# pqc-rev1_1.net
KiCad netlist of a schematic drawn in EAGLE
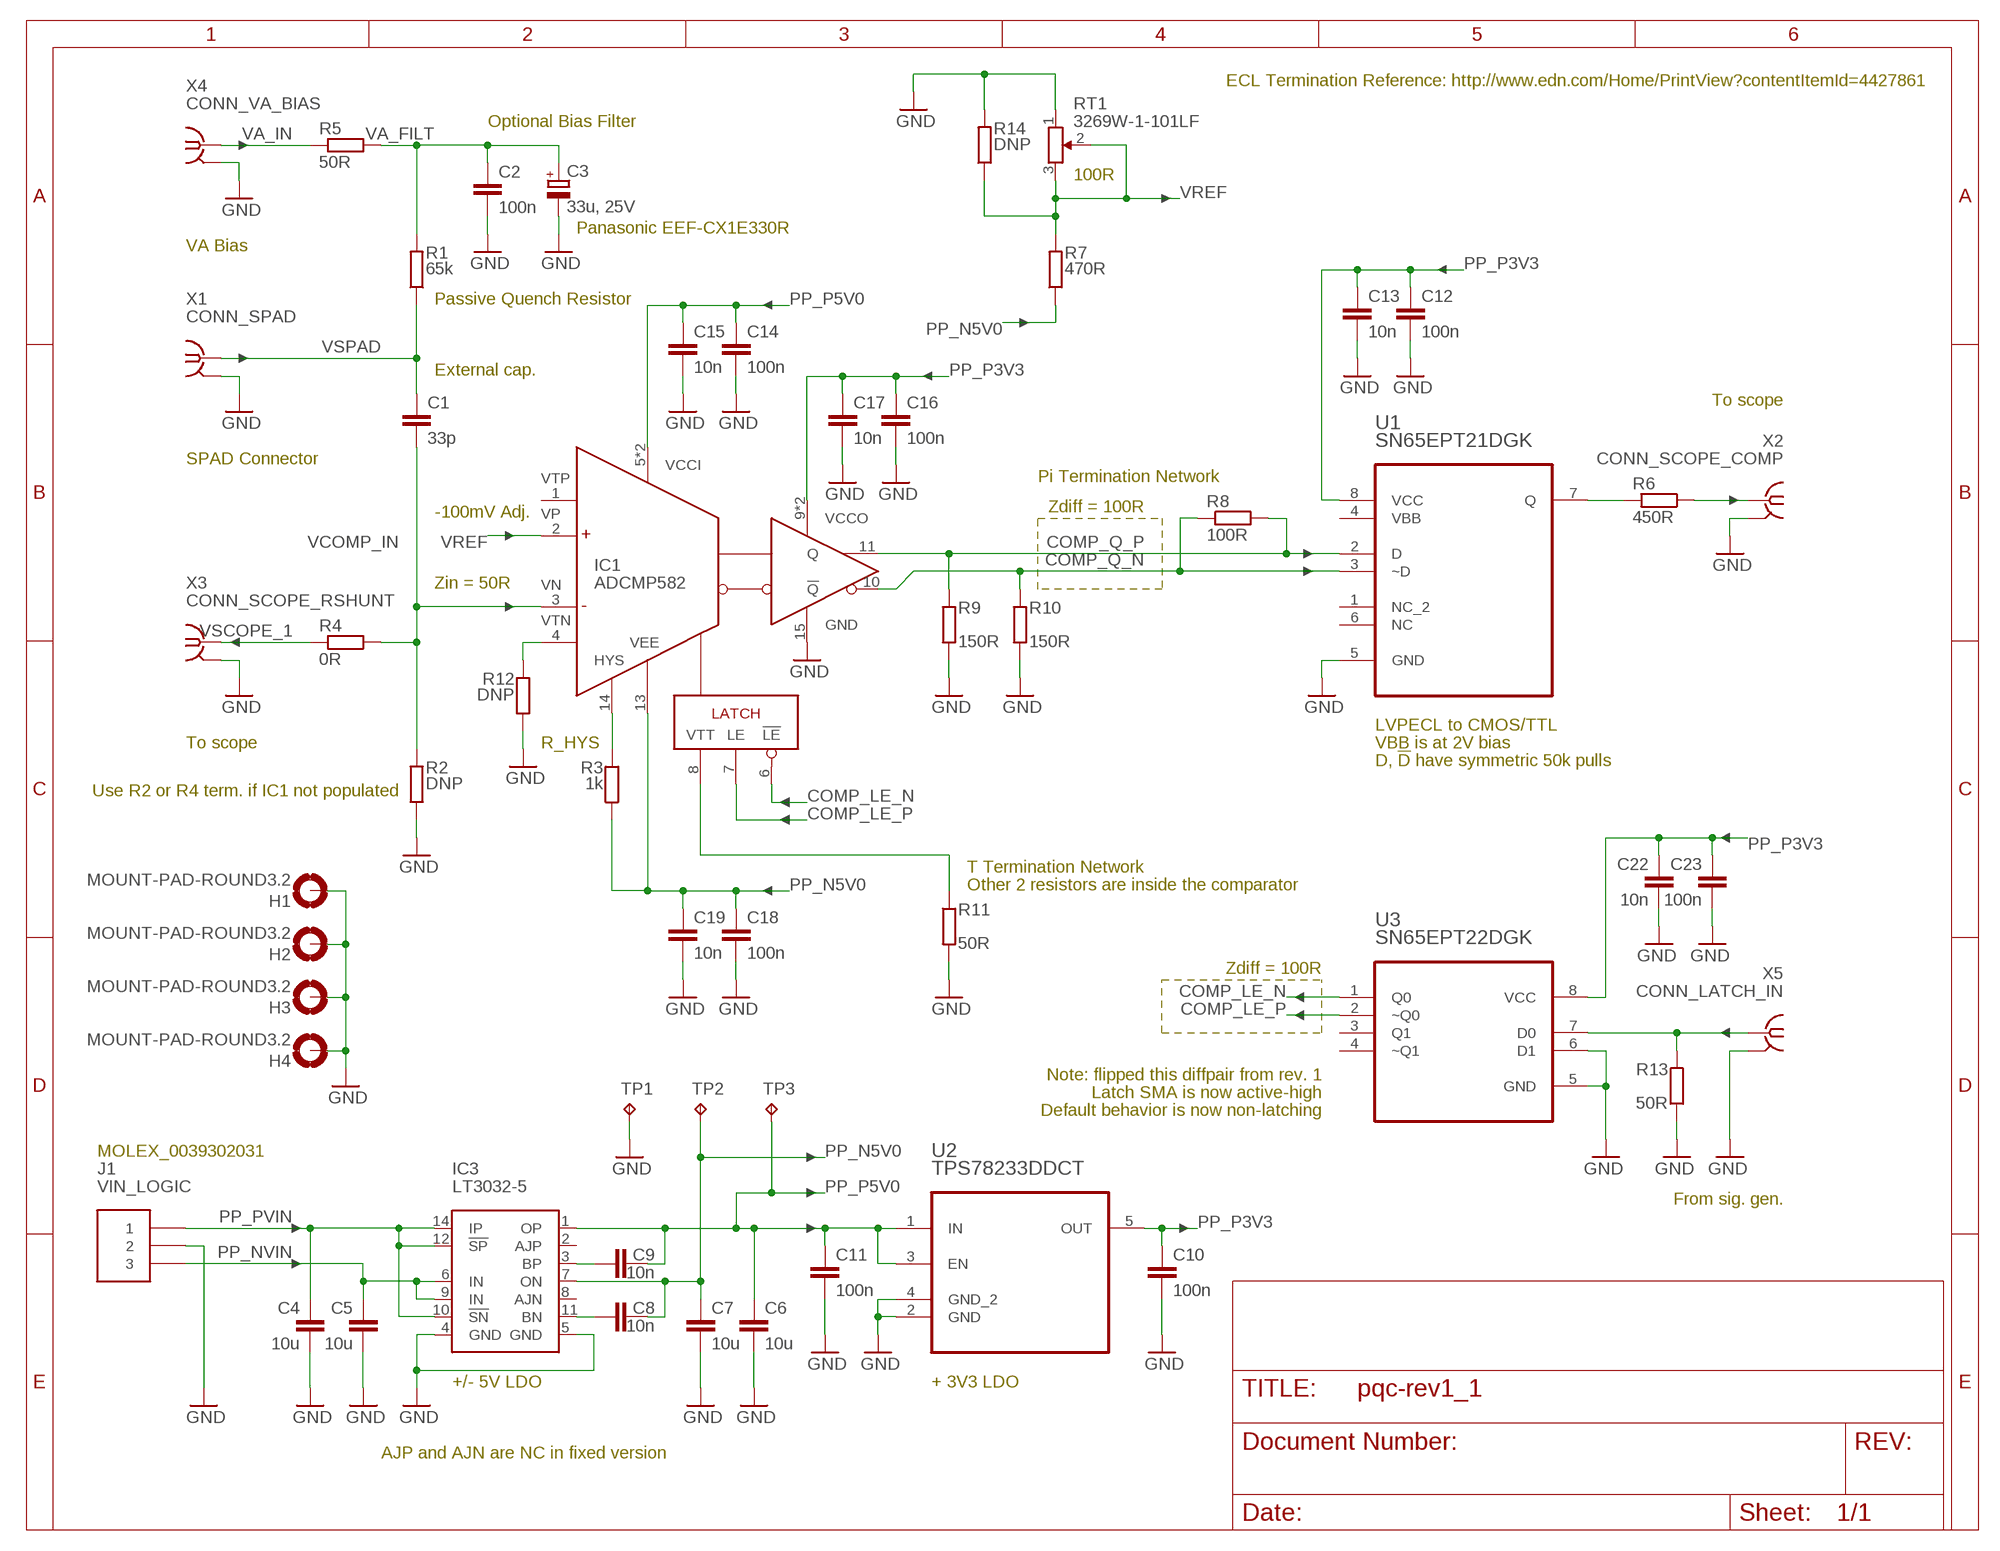
[diagram p0: schematic, sheet 1]

(export (version "E")
  (design (tool "Eeschema 10.0.6"))
  (components
    (comp (ref "C1")
      (value "33p")
      (footprint "eagle-import:C0805")
      (libsource (lib "eagle-import") (part "C-EUC0805"))
    )
    (comp (ref "C2")
      (value "100n")
      (footprint "eagle-import:C0805")
      (libsource (lib "eagle-import") (part "C-EUC0805"))
    )
    (comp (ref "C3")
      (value "33u, 25V")
      (footprint "eagle-import:CT7343")
      (libsource (lib "eagle-import") (part "CPOL-EUCT7343"))
    )
    (comp (ref "C4")
      (value "10u")
      (footprint "eagle-import:C1206")
      (libsource (lib "eagle-import") (part "C-EUC1206"))
    )
    (comp (ref "C5")
      (value "10u")
      (footprint "eagle-import:C1206")
      (libsource (lib "eagle-import") (part "C-EUC1206"))
    )
    (comp (ref "C6")
      (value "10u")
      (footprint "eagle-import:C1206")
      (libsource (lib "eagle-import") (part "C-EUC1206"))
    )
    (comp (ref "C7")
      (value "10u")
      (footprint "eagle-import:C1206")
      (libsource (lib "eagle-import") (part "C-EUC1206"))
    )
    (comp (ref "C8")
      (value "10n")
      (footprint "eagle-import:C0603")
      (libsource (lib "eagle-import") (part "C-EUC0603"))
    )
    (comp (ref "C9")
      (value "10n")
      (footprint "eagle-import:C0603")
      (libsource (lib "eagle-import") (part "C-EUC0603"))
    )
    (comp (ref "C10")
      (value "100n")
      (footprint "eagle-import:C0603")
      (libsource (lib "eagle-import") (part "C-EUC0603"))
    )
    (comp (ref "C11")
      (value "100n")
      (footprint "eagle-import:C0603")
      (libsource (lib "eagle-import") (part "C-EUC0603"))
    )
    (comp (ref "C12")
      (value "100n")
      (footprint "eagle-import:C0603")
      (libsource (lib "eagle-import") (part "C-EUC0603"))
    )
    (comp (ref "C13")
      (value "10n")
      (footprint "eagle-import:C0603")
      (libsource (lib "eagle-import") (part "C-EUC0603"))
    )
    (comp (ref "C14")
      (value "100n")
      (footprint "eagle-import:C0603")
      (libsource (lib "eagle-import") (part "C-EUC0603"))
    )
    (comp (ref "C15")
      (value "10n")
      (footprint "eagle-import:C0603")
      (libsource (lib "eagle-import") (part "C-EUC0603"))
    )
    (comp (ref "C16")
      (value "100n")
      (footprint "eagle-import:C0603")
      (libsource (lib "eagle-import") (part "C-EUC0603"))
    )
    (comp (ref "C17")
      (value "10n")
      (footprint "eagle-import:C0603")
      (libsource (lib "eagle-import") (part "C-EUC0603"))
    )
    (comp (ref "C18")
      (value "100n")
      (footprint "eagle-import:C0603")
      (libsource (lib "eagle-import") (part "C-EUC0603"))
    )
    (comp (ref "C19")
      (value "10n")
      (footprint "eagle-import:C0603")
      (libsource (lib "eagle-import") (part "C-EUC0603"))
    )
    (comp (ref "C22")
      (value "10n")
      (footprint "eagle-import:C0603")
      (libsource (lib "eagle-import") (part "C-EUC0603"))
    )
    (comp (ref "C23")
      (value "100n")
      (footprint "eagle-import:C0603")
      (libsource (lib "eagle-import") (part "C-EUC0603"))
    )
    (comp (ref "H1")
      (value "MOUNT-PAD-ROUND3.2")
      (footprint "eagle-import:3,2-PAD")
      (libsource (lib "eagle-import") (part "MOUNT-PAD-ROUND3.2"))
    )
    (comp (ref "H2")
      (value "MOUNT-PAD-ROUND3.2")
      (footprint "eagle-import:3,2-PAD")
      (libsource (lib "eagle-import") (part "MOUNT-PAD-ROUND3.2"))
    )
    (comp (ref "H3")
      (value "MOUNT-PAD-ROUND3.2")
      (footprint "eagle-import:3,2-PAD")
      (libsource (lib "eagle-import") (part "MOUNT-PAD-ROUND3.2"))
    )
    (comp (ref "H4")
      (value "MOUNT-PAD-ROUND3.2")
      (footprint "eagle-import:3,2-PAD")
      (libsource (lib "eagle-import") (part "MOUNT-PAD-ROUND3.2"))
    )
    (comp (ref "IC1")
      (value "ADCMP582")
      (footprint "eagle-import:QFN50P300X300X80-16N")
      (libsource (lib "eagle-import") (part "ADCMP582"))
    )
    (comp (ref "IC3")
      (value "LT3032-5")
      (footprint "eagle-import:DFN14-4X3DE")
      (libsource (lib "eagle-import") (part "LT3032"))
    )
    (comp (ref "J1")
      (value "VIN_LOGIC")
      (footprint "eagle-import:CONN_MOLEX_3PIN_MINI-FIT_JR")
      (libsource (lib "eagle-import") (part "CONN_MOLEX_3PIN_MINI-FIT_JR"))
    )
    (comp (ref "R1")
      (value "65k")
      (footprint "eagle-import:R0805")
      (libsource (lib "eagle-import") (part "R-EU_R0805"))
    )
    (comp (ref "R2")
      (value "DNP")
      (footprint "eagle-import:R0603")
      (libsource (lib "eagle-import") (part "R-EU_R0603"))
    )
    (comp (ref "R3")
      (value "1k")
      (footprint "eagle-import:R0805")
      (libsource (lib "eagle-import") (part "R-EU_R0805"))
    )
    (comp (ref "R4")
      (value "0R")
      (footprint "eagle-import:R0603")
      (libsource (lib "eagle-import") (part "R-EU_R0603"))
    )
    (comp (ref "R5")
      (value "50R")
      (footprint "eagle-import:R0805")
      (libsource (lib "eagle-import") (part "R-EU_R0805"))
    )
    (comp (ref "R6")
      (value "450R")
      (footprint "eagle-import:R0603")
      (libsource (lib "eagle-import") (part "R-EU_R0603"))
    )
    (comp (ref "R7")
      (value "470R")
      (footprint "eagle-import:R0805")
      (libsource (lib "eagle-import") (part "R-EU_R0805"))
    )
    (comp (ref "R8")
      (value "100R")
      (footprint "eagle-import:R0603")
      (libsource (lib "eagle-import") (part "R-EU_R0603"))
    )
    (comp (ref "R9")
      (value "150R")
      (footprint "eagle-import:R0603")
      (libsource (lib "eagle-import") (part "R-EU_R0603"))
    )
    (comp (ref "R10")
      (value "150R")
      (footprint "eagle-import:R0603")
      (libsource (lib "eagle-import") (part "R-EU_R0603"))
    )
    (comp (ref "R11")
      (value "50R")
      (footprint "eagle-import:R0603")
      (libsource (lib "eagle-import") (part "R-EU_R0603"))
    )
    (comp (ref "R12")
      (value "DNP")
      (footprint "eagle-import:R0603")
      (libsource (lib "eagle-import") (part "R-EU_R0603"))
    )
    (comp (ref "R13")
      (value "50R")
      (footprint "eagle-import:R0603")
      (libsource (lib "eagle-import") (part "R-EU_R0603"))
    )
    (comp (ref "R14")
      (value "DNP")
      (footprint "eagle-import:R0805")
      (libsource (lib "eagle-import") (part "R-EU_R0805"))
    )
    (comp (ref "RT1")
      (value "3269W-1-101LF")
      (footprint "eagle-import:3269W")
      (libsource (lib "eagle-import") (part "BOURNS_3269WX"))
    )
    (comp (ref "TP1")
      (value "TPTP20R")
      (footprint "eagle-import:TP20R")
      (libsource (lib "eagle-import") (part "TPTP20R"))
    )
    (comp (ref "TP2")
      (value "TPTP20R")
      (footprint "eagle-import:TP20R")
      (libsource (lib "eagle-import") (part "TPTP20R"))
    )
    (comp (ref "TP3")
      (value "TPTP20R")
      (footprint "eagle-import:TP20R")
      (libsource (lib "eagle-import") (part "TPTP20R"))
    )
    (comp (ref "U1")
      (value "SN65EPT21DGK")
      (footprint "eagle-import:SOP65P490X110-8N")
      (libsource (lib "eagle-import") (part "SN65EPT21DGK"))
    )
    (comp (ref "U2")
      (value "TPS78233DDCT")
      (footprint "eagle-import:SOT95P280X110-5N")
      (libsource (lib "eagle-import") (part "TPS78233DDCT"))
    )
    (comp (ref "U3")
      (value "SN65EPT22DGK")
      (footprint "eagle-import:SOP65P490X110-8N")
      (libsource (lib "eagle-import") (part "SN65EPT22DGK"))
    )
    (comp (ref "X1")
      (value "CONN_SPAD")
      (footprint "eagle-import:J502-ND-142-0711-871_876")
      (fields (field (name "MF") "JOHNSON COMPONENTS") (field (name "MPN") "142-0711-871"))
      (libsource (lib "eagle-import") (part "SMA-142-0711-871/876"))
    )
    (comp (ref "X2")
      (value "CONN_SCOPE_COMP")
      (footprint "eagle-import:J502-ND-142-0711-871_876")
      (fields (field (name "MF") "JOHNSON COMPONENTS") (field (name "MPN") "142-0711-871"))
      (libsource (lib "eagle-import") (part "SMA-142-0711-871/876"))
    )
    (comp (ref "X3")
      (value "CONN_SCOPE_RSHUNT")
      (footprint "eagle-import:J502-ND-142-0711-871_876")
      (fields (field (name "MF") "JOHNSON COMPONENTS") (field (name "MPN") "142-0711-871"))
      (libsource (lib "eagle-import") (part "SMA-142-0711-871/876"))
    )
    (comp (ref "X4")
      (value "CONN_VA_BIAS")
      (footprint "eagle-import:J502-ND-142-0711-871_876")
      (fields (field (name "MF") "JOHNSON COMPONENTS") (field (name "MPN") "142-0711-871"))
      (libsource (lib "eagle-import") (part "SMA-142-0711-871/876"))
    )
    (comp (ref "X5")
      (value "CONN_LATCH_IN")
      (footprint "eagle-import:J502-ND-142-0711-871_876")
      (fields
        (field (name "MF") "JOHNSON COMPONENTS")
        (field (name "MPN") "142-0711-871")
        (field (name "MF_1") "JOHNSON COMPONENTS")
        (field (name "MPN_1") "142-0711-871")
        (field (name "OC_FARNELL") "unknown")
        (field (name "OC_NEWARK") "01C1639")
      )
      (libsource (lib "eagle-import") (part "SMA-142-0711-871/876"))
    )
  )
  (nets
    (net (code "1") (name "/COMP_LE_N") (class "Default")
      (node (ref "IC1") (pin "6") (pinfunction "~{LE}_6") (pintype "bidirectional"))
      (node (ref "U3") (pin "1") (pinfunction "Q0_1") (pintype "output"))
    )
    (net (code "2") (name "/COMP_LE_P") (class "Default")
      (node (ref "IC1") (pin "7") (pinfunction "LE_7") (pintype "bidirectional"))
      (node (ref "U3") (pin "2") (pinfunction "~{Q0}_2") (pintype "output"))
    )
    (net (code "3") (name "/COMP_Q_N") (class "Default")
      (node (ref "IC1") (pin "10") (pinfunction "~{Q}_10") (pintype "bidirectional"))
      (node (ref "R10") (pin "1") (pinfunction "1_1") (pintype "passive"))
      (node (ref "R8") (pin "1") (pinfunction "1_1") (pintype "passive"))
      (node (ref "U1") (pin "3") (pinfunction "~{D}_3") (pintype "input"))
    )
    (net (code "4") (name "/COMP_Q_P") (class "Default")
      (node (ref "IC1") (pin "11") (pinfunction "Q_11") (pintype "bidirectional"))
      (node (ref "R8") (pin "2") (pinfunction "2_2") (pintype "passive"))
      (node (ref "R9") (pin "1") (pinfunction "1_1") (pintype "passive"))
      (node (ref "U1") (pin "2") (pinfunction "D_2") (pintype "input"))
    )
    (net (code "5") (name "/PP_N5V0") (class "Default")
      (node (ref "C18") (pin "1") (pinfunction "1_1") (pintype "passive"))
      (node (ref "C19") (pin "1") (pinfunction "1_1") (pintype "passive"))
      (node (ref "C7") (pin "1") (pinfunction "1_1") (pintype "passive"))
      (node (ref "C8") (pin "2") (pinfunction "2_2") (pintype "passive"))
      (node (ref "IC1") (pin "13") (pinfunction "VEE_13") (pintype "bidirectional"))
      (node (ref "IC3") (pin "7") (pinfunction "ON_7") (pintype "power_in"))
      (node (ref "R3") (pin "1") (pinfunction "1_1") (pintype "passive"))
      (node (ref "R7") (pin "1") (pinfunction "1_1") (pintype "passive"))
      (node (ref "TP2") (pin "TP") (pinfunction "TP_TP") (pintype "input"))
    )
    (net (code "6") (name "/PP_NVIN") (class "Default")
      (node (ref "C5") (pin "1") (pinfunction "1_1") (pintype "passive"))
      (node (ref "IC3") (pin "6") (pinfunction "IN_6") (pintype "power_in"))
      (node (ref "IC3") (pin "9") (pinfunction "IN_9") (pintype "power_in"))
      (node (ref "J1") (pin "3") (pinfunction "3_3") (pintype "bidirectional"))
    )
    (net (code "7") (name "/PP_P3V3") (class "Default")
      (node (ref "C10") (pin "1") (pinfunction "1_1") (pintype "passive"))
      (node (ref "C12") (pin "1") (pinfunction "1_1") (pintype "passive"))
      (node (ref "C13") (pin "1") (pinfunction "1_1") (pintype "passive"))
      (node (ref "C16") (pin "1") (pinfunction "1_1") (pintype "passive"))
      (node (ref "C17") (pin "1") (pinfunction "1_1") (pintype "passive"))
      (node (ref "C22") (pin "1") (pinfunction "1_1") (pintype "passive"))
      (node (ref "C23") (pin "1") (pinfunction "1_1") (pintype "passive"))
      (node (ref "IC1") (pin "12") (pinfunction "VCCO_12") (pintype "bidirectional"))
      (node (ref "IC1") (pin "9") (pinfunction "VCCO_9") (pintype "bidirectional"))
      (node (ref "U1") (pin "8") (pinfunction "VCC_8") (pintype "power_in"))
      (node (ref "U2") (pin "5") (pinfunction "OUT_5") (pintype "output"))
      (node (ref "U3") (pin "8") (pinfunction "VCC_8") (pintype "power_in"))
    )
    (net (code "8") (name "/PP_P5V0") (class "Default")
      (node (ref "C11") (pin "1") (pinfunction "1_1") (pintype "passive"))
      (node (ref "C14") (pin "1") (pinfunction "1_1") (pintype "passive"))
      (node (ref "C15") (pin "1") (pinfunction "1_1") (pintype "passive"))
      (node (ref "C6") (pin "1") (pinfunction "1_1") (pintype "passive"))
      (node (ref "C9") (pin "2") (pinfunction "2_2") (pintype "passive"))
      (node (ref "IC1") (pin "16") (pinfunction "VCCI_16") (pintype "bidirectional"))
      (node (ref "IC1") (pin "5") (pinfunction "VCCI_5") (pintype "bidirectional"))
      (node (ref "IC3") (pin "1") (pinfunction "OP_1") (pintype "power_in"))
      (node (ref "TP3") (pin "TP") (pinfunction "TP_TP") (pintype "input"))
      (node (ref "U2") (pin "1") (pinfunction "IN_1") (pintype "input"))
      (node (ref "U2") (pin "3") (pinfunction "EN_3") (pintype "input"))
    )
    (net (code "9") (name "/PP_PVIN") (class "Default")
      (node (ref "C4") (pin "1") (pinfunction "1_1") (pintype "passive"))
      (node (ref "IC3") (pin "10") (pinfunction "~{SN}_10") (pintype "bidirectional"))
      (node (ref "IC3") (pin "12") (pinfunction "~{SP}_12") (pintype "bidirectional"))
      (node (ref "IC3") (pin "14") (pinfunction "IP_14") (pintype "power_in"))
      (node (ref "J1") (pin "1") (pinfunction "1_1") (pintype "bidirectional"))
    )
    (net (code "10") (name "/VA_FILT") (class "Default")
      (node (ref "C2") (pin "1") (pinfunction "1_1") (pintype "passive"))
      (node (ref "C3") (pin "+") (pinfunction "+_+") (pintype "passive"))
      (node (ref "R1") (pin "2") (pinfunction "2_2") (pintype "passive"))
      (node (ref "R5") (pin "1") (pinfunction "1_1") (pintype "passive"))
    )
    (net (code "11") (name "/VA_IN") (class "Default")
      (node (ref "R5") (pin "2") (pinfunction "2_2") (pintype "passive"))
      (node (ref "X4") (pin "1") (pinfunction "1_1") (pintype "passive"))
    )
    (net (code "12") (name "/VBB") (class "Default")
      (node (ref "U1") (pin "4") (pinfunction "VBB_4") (pintype "power_in"))
    )
    (net (code "13") (name "/VCOMP_IN") (class "Default")
      (node (ref "C1") (pin "2") (pinfunction "2_2") (pintype "passive"))
      (node (ref "IC1") (pin "3") (pinfunction "VN_3") (pintype "bidirectional"))
      (node (ref "R2") (pin "2") (pinfunction "2_2") (pintype "passive"))
      (node (ref "R4") (pin "1") (pinfunction "1_1") (pintype "passive"))
    )
    (net (code "14") (name "/VREF") (class "Default")
      (node (ref "IC1") (pin "2") (pinfunction "VP_2") (pintype "bidirectional"))
      (node (ref "R14") (pin "1") (pinfunction "1_1") (pintype "passive"))
      (node (ref "R7") (pin "2") (pinfunction "2_2") (pintype "passive"))
      (node (ref "RT1") (pin "2") (pinfunction "2_2") (pintype "bidirectional"))
      (node (ref "RT1") (pin "3") (pinfunction "3_3") (pintype "bidirectional"))
    )
    (net (code "15") (name "/VSCOPE_1") (class "Default")
      (node (ref "R4") (pin "2") (pinfunction "2_2") (pintype "passive"))
      (node (ref "X3") (pin "1") (pinfunction "1_1") (pintype "passive"))
    )
    (net (code "16") (name "/VSPAD") (class "Default")
      (node (ref "C1") (pin "1") (pinfunction "1_1") (pintype "passive"))
      (node (ref "R1") (pin "1") (pinfunction "1_1") (pintype "passive"))
      (node (ref "X1") (pin "1") (pinfunction "1_1") (pintype "passive"))
    )
    (net (code "17") (name "GND") (class "Default")
      (node (ref "C10") (pin "2") (pinfunction "2_2") (pintype "passive"))
      (node (ref "C11") (pin "2") (pinfunction "2_2") (pintype "passive"))
      (node (ref "C12") (pin "2") (pinfunction "2_2") (pintype "passive"))
      (node (ref "C13") (pin "2") (pinfunction "2_2") (pintype "passive"))
      (node (ref "C14") (pin "2") (pinfunction "2_2") (pintype "passive"))
      (node (ref "C15") (pin "2") (pinfunction "2_2") (pintype "passive"))
      (node (ref "C16") (pin "2") (pinfunction "2_2") (pintype "passive"))
      (node (ref "C17") (pin "2") (pinfunction "2_2") (pintype "passive"))
      (node (ref "C18") (pin "2") (pinfunction "2_2") (pintype "passive"))
      (node (ref "C19") (pin "2") (pinfunction "2_2") (pintype "passive"))
      (node (ref "C2") (pin "2") (pinfunction "2_2") (pintype "passive"))
      (node (ref "C22") (pin "2") (pinfunction "2_2") (pintype "passive"))
      (node (ref "C23") (pin "2") (pinfunction "2_2") (pintype "passive"))
      (node (ref "C3") (pin "-") (pinfunction "-_-") (pintype "passive"))
      (node (ref "C4") (pin "2") (pinfunction "2_2") (pintype "passive"))
      (node (ref "C5") (pin "2") (pinfunction "2_2") (pintype "passive"))
      (node (ref "C6") (pin "2") (pinfunction "2_2") (pintype "passive"))
      (node (ref "C7") (pin "2") (pinfunction "2_2") (pintype "passive"))
      (node (ref "H1") (pin "B3,2") (pinfunction "MOUNT_B3,2") (pintype "passive"))
      (node (ref "H2") (pin "B3,2") (pinfunction "MOUNT_B3,2") (pintype "passive"))
      (node (ref "H3") (pin "B3,2") (pinfunction "MOUNT_B3,2") (pintype "passive"))
      (node (ref "H4") (pin "B3,2") (pinfunction "MOUNT_B3,2") (pintype "passive"))
      (node (ref "IC1") (pin "15") (pinfunction "GND_15") (pintype "bidirectional"))
      (node (ref "IC3") (pin "4") (pinfunction "GND_4") (pintype "power_in"))
      (node (ref "IC3") (pin "5") (pinfunction "GND_5") (pintype "power_in"))
      (node (ref "J1") (pin "2") (pinfunction "2_2") (pintype "bidirectional"))
      (node (ref "R10") (pin "2") (pinfunction "2_2") (pintype "passive"))
      (node (ref "R11") (pin "2") (pinfunction "2_2") (pintype "passive"))
      (node (ref "R12") (pin "1") (pinfunction "1_1") (pintype "passive"))
      (node (ref "R13") (pin "2") (pinfunction "2_2") (pintype "passive"))
      (node (ref "R14") (pin "2") (pinfunction "2_2") (pintype "passive"))
      (node (ref "R2") (pin "1") (pinfunction "1_1") (pintype "passive"))
      (node (ref "R9") (pin "2") (pinfunction "2_2") (pintype "passive"))
      (node (ref "RT1") (pin "1") (pinfunction "1_1") (pintype "bidirectional"))
      (node (ref "TP1") (pin "TP") (pinfunction "TP_TP") (pintype "input"))
      (node (ref "U1") (pin "5") (pinfunction "GND_5") (pintype "passive"))
      (node (ref "U2") (pin "2") (pinfunction "GND_2") (pintype "passive"))
      (node (ref "U2") (pin "4") (pinfunction "GND_2_4") (pintype "passive"))
      (node (ref "U3") (pin "5") (pinfunction "GND_5") (pintype "passive"))
      (node (ref "U3") (pin "6") (pinfunction "D1_6") (pintype "input"))
      (node (ref "X1") (pin "G@1") (pinfunction "GND_G@1") (pintype "power_in"))
      (node (ref "X2") (pin "G@1") (pinfunction "GND_G@1") (pintype "power_in"))
      (node (ref "X3") (pin "G@1") (pinfunction "GND_G@1") (pintype "power_in"))
      (node (ref "X4") (pin "G@1") (pinfunction "GND_G@1") (pintype "power_in"))
      (node (ref "X5") (pin "G@1") (pinfunction "GND_G@1") (pintype "power_in"))
    )
    (net (code "18") (name "Net-(IC1-HYS)") (class "Default")
      (node (ref "IC1") (pin "14") (pinfunction "HYS_14") (pintype "bidirectional"))
      (node (ref "R3") (pin "2") (pinfunction "2_2") (pintype "passive"))
    )
    (net (code "19") (name "Net-(IC1-VTN)") (class "Default")
      (node (ref "IC1") (pin "4") (pinfunction "VTN_4") (pintype "bidirectional"))
      (node (ref "R12") (pin "2") (pinfunction "2_2") (pintype "passive"))
    )
    (net (code "20") (name "Net-(IC1-VTT)") (class "Default")
      (node (ref "IC1") (pin "8") (pinfunction "VTT_8") (pintype "bidirectional"))
      (node (ref "R11") (pin "1") (pinfunction "1_1") (pintype "passive"))
    )
    (net (code "21") (name "Net-(IC3-BN)") (class "Default")
      (node (ref "C8") (pin "1") (pinfunction "1_1") (pintype "passive"))
      (node (ref "IC3") (pin "11") (pinfunction "BN_11") (pintype "bidirectional"))
    )
    (net (code "22") (name "Net-(IC3-BP)") (class "Default")
      (node (ref "C9") (pin "1") (pinfunction "1_1") (pintype "passive"))
      (node (ref "IC3") (pin "3") (pinfunction "BP_3") (pintype "bidirectional"))
    )
    (net (code "23") (name "Net-(R6-Pad1)") (class "Default")
      (node (ref "R6") (pin "1") (pinfunction "1_1") (pintype "passive"))
      (node (ref "X2") (pin "1") (pinfunction "1_1") (pintype "passive"))
    )
    (net (code "24") (name "Net-(U1-Q)") (class "Default")
      (node (ref "R6") (pin "2") (pinfunction "2_2") (pintype "passive"))
      (node (ref "U1") (pin "7") (pinfunction "Q_7") (pintype "output"))
    )
    (net (code "25") (name "Net-(U3-D0)") (class "Default")
      (node (ref "R13") (pin "1") (pinfunction "1_1") (pintype "passive"))
      (node (ref "U3") (pin "7") (pinfunction "D0_7") (pintype "input"))
      (node (ref "X5") (pin "1") (pinfunction "1_1") (pintype "passive"))
    )
    (net (code "26") (name "unconnected-(IC1-VTP-Pad1)") (class "Default")
      (node (ref "IC1") (pin "1") (pinfunction "VTP_1") (pintype "bidirectional"))
    )
    (net (code "27") (name "unconnected-(IC3-AJN-Pad8)") (class "Default")
      (node (ref "IC3") (pin "8") (pinfunction "AJN_8") (pintype "bidirectional"))
    )
    (net (code "28") (name "unconnected-(IC3-AJP-Pad2)") (class "Default")
      (node (ref "IC3") (pin "2") (pinfunction "AJP_2") (pintype "bidirectional"))
    )
    (net (code "29") (name "unconnected-(U1-NC-Pad6)") (class "Default")
      (node (ref "U1") (pin "6") (pinfunction "NC_6") (pintype "no_connect"))
    )
    (net (code "30") (name "unconnected-(U1-NC_2-Pad1)") (class "Default")
      (node (ref "U1") (pin "1") (pinfunction "NC_2_1") (pintype "no_connect"))
    )
    (net (code "31") (name "unconnected-(U3-Q1-Pad3)") (class "Default")
      (node (ref "U3") (pin "3") (pinfunction "Q1_3") (pintype "output"))
    )
    (net (code "32") (name "unconnected-(U3-~{Q1}-Pad4)") (class "Default")
      (node (ref "U3") (pin "4") (pinfunction "~{Q1}_4") (pintype "output"))
    )
  )
)
